# Power.net
KiCad netlist of a schematic drawn in Altium Designer
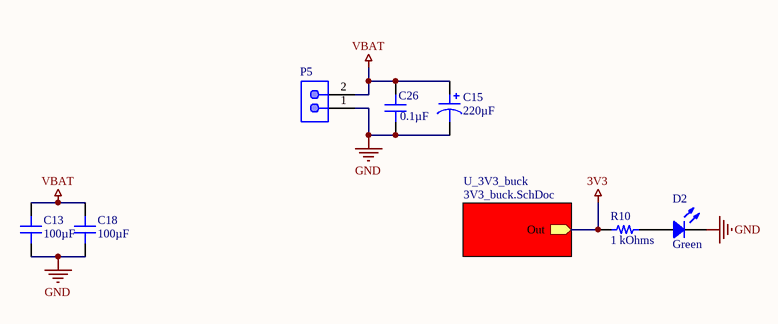
[diagram p0: Power.SchDoc]

(export (version "E")
  (design (tool "Eeschema 10.0.6"))
  (components
    (comp (ref "C13")
      (value "100µF")
      (footprint "CAP 1210_3225 - 2.8MM")
      (description "CAP CER 100UF 16V X5R 1210")
      (fields (field (name "PART NUMBER") "EMK325ABJ107MM-P") (field (name "MANUFACTURER") "Taiyo Yuden"))
      (libsource (lib "Celestial Altium Library - altium_library") (part "Capacitor"))
    )
    (comp (ref "C15")
      (value "220µF")
      (footprint "CAP POL 2917_7343")
      (description "CAP TANT 220UF 10% 16V 2917")
      (fields (field (name "PART NUMBER") "T510X227K016ATE040") (field (name "MANUFACTURER") "KEMET"))
      (libsource (lib "Celestial Altium Library - altium_library") (part "Polarised Capacitor"))
    )
    (comp (ref "C18")
      (value "100µF")
      (footprint "CAP 1210_3225 - 2.8MM")
      (description "CAP CER 100UF 16V X5R 1210")
      (fields (field (name "PART NUMBER") "EMK325ABJ107MM-P") (field (name "MANUFACTURER") "Taiyo Yuden"))
      (libsource (lib "Celestial Altium Library - altium_library") (part "Capacitor"))
    )
    (comp (ref "C26")
      (value "0.1µF")
      (footprint "CAP 0603_1608")
      (description "CAP CER 0.1UF 100V 0603 EPOXY")
      (fields
        (field (name "PART NUMBER") "GCG188R92A104KA03D")
        (field (name "MANUFACTURER") "Murata Electronics")
      )
      (libsource (lib "Celestial Altium Library - altium_library") (part "Capacitor"))
    )
    (comp (ref "D2")
      (value "Green")
      (footprint "LED 0603_1608 GREEN")
      (description "1.6X0.8MM LC GREEN PIXSOLED DOME")
      (fields (field (name "PART NUMBER") "XZCDGK53W-8VF") (field (name "MANUFACTURER") "SunLED"))
      (libsource (lib "Celestial Altium Library - altium_library") (part "LED"))
    )
    (comp (ref "P5")
      (value "2 pin 2mm JST Male")
      (footprint "2pin - 2mm JST male")
      (libsource (lib "IC") (part "2 pin 2mm JST Male"))
    )
    (comp (ref "R10")
      (value "1 kOhms")
      (footprint "RES 0603_1608")
      (description "RES 1K OHM 0.5% 1/10W 0603")
      (fields
        (field (name "PART NUMBER") "RNCF0603DTE1K00")
        (field (name "MANUFACTURER") "Stackpole Electronics Inc")
      )
      (libsource (lib "Celestial Altium Library - altium_library") (part "Resistor"))
    )
  )
  (nets
    (net (code "1") (name "3V3") (class "Default")
      (node (ref "R10") (pin "1") (pinfunction "1_1") (pintype "passive"))
    )
    (net (code "2") (name "GND") (class "Default")
      (node (ref "C13") (pin "1") (pinfunction "1_1") (pintype "passive"))
      (node (ref "C15") (pin "2") (pinfunction "2_2") (pintype "passive"))
      (node (ref "C18") (pin "1") (pinfunction "1_1") (pintype "passive"))
      (node (ref "C26") (pin "2") (pinfunction "2_2") (pintype "passive"))
      (node (ref "D2") (pin "2") (pinfunction "2_2") (pintype "passive"))
      (node (ref "P5") (pin "1") (pinfunction "1_1") (pintype "passive"))
    )
    (net (code "3") (name "Net-(D2-Pad1)") (class "Default")
      (node (ref "D2") (pin "1") (pinfunction "1_1") (pintype "passive"))
      (node (ref "R10") (pin "2") (pinfunction "2_2") (pintype "passive"))
    )
    (net (code "4") (name "VBAT") (class "Default")
      (node (ref "C13") (pin "2") (pinfunction "2_2") (pintype "passive"))
      (node (ref "C15") (pin "1") (pinfunction "1_1") (pintype "passive"))
      (node (ref "C18") (pin "2") (pinfunction "2_2") (pintype "passive"))
      (node (ref "C26") (pin "1") (pinfunction "1_1") (pintype "passive"))
      (node (ref "P5") (pin "2") (pinfunction "2_2") (pintype "passive"))
    )
  )
)
